# FM-Superregenerative-Receiver-2.net
KiCad netlist of a schematic drawn in EAGLE
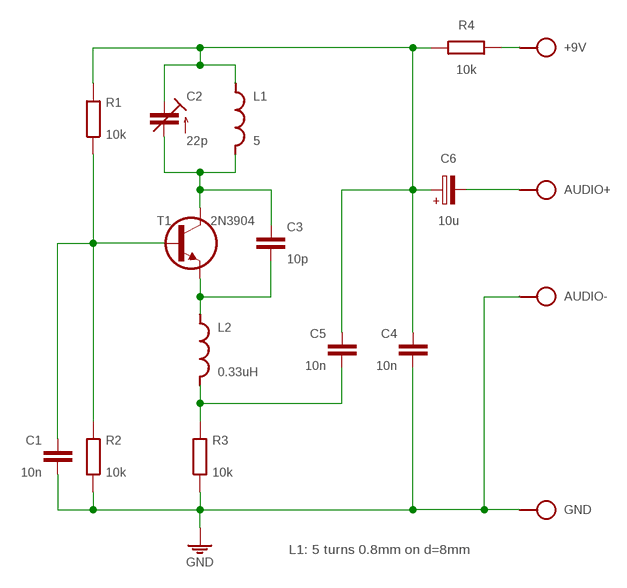
[diagram p0: schematic, sheet 1]

(export (version "E")
  (design (tool "Eeschema 10.0.6"))
  (components
    (comp (ref "+9V")
      (value "SPAD")
      (footprint "eagle-import:SPAD")
      (libsource (lib "eagle-import") (part "SPAD"))
    )
    (comp (ref "AUDIO+")
      (value "SPAD")
      (footprint "eagle-import:SPAD")
      (libsource (lib "eagle-import") (part "SPAD"))
    )
    (comp (ref "AUDIO-")
      (value "SPAD")
      (footprint "eagle-import:SPAD")
      (libsource (lib "eagle-import") (part "SPAD"))
    )
    (comp (ref "C1")
      (value "10n")
      (footprint "eagle-import:C050-025X075")
      (libsource (lib "eagle-import") (part "C050-025X075"))
    )
    (comp (ref "C2")
      (value "22p")
      (footprint "eagle-import:TRIM-2222-808")
      (libsource (lib "eagle-import") (part "C-TR-PH20127"))
    )
    (comp (ref "C3")
      (value "10p")
      (footprint "eagle-import:C050-020X036")
      (libsource (lib "eagle-import") (part "C050-020X036"))
    )
    (comp (ref "C4")
      (value "10n")
      (footprint "eagle-import:C050-025X075")
      (libsource (lib "eagle-import") (part "C050-025X075"))
    )
    (comp (ref "C5")
      (value "10n")
      (footprint "eagle-import:C050-025X075")
      (libsource (lib "eagle-import") (part "C050-025X075"))
    )
    (comp (ref "C6")
      (value "10u")
      (footprint "eagle-import:E2,5-3")
      (libsource (lib "eagle-import") (part "CPOLE2,5-3"))
    )
    (comp (ref "GND")
      (value "SPAD")
      (footprint "eagle-import:SPAD")
      (libsource (lib "eagle-import") (part "SPAD"))
    )
    (comp (ref "L1")
      (value "5")
      (footprint "eagle-import:L-02_5V")
      (libsource (lib "eagle-import") (part "L-SHORT02/5"))
    )
    (comp (ref "L2")
      (value "0.33uH")
      (footprint "eagle-import:L-02_5V")
      (libsource (lib "eagle-import") (part "L-SHORT02/5"))
    )
    (comp (ref "R1")
      (value "10k")
      (footprint "eagle-import:0204_10")
      (libsource (lib "eagle-import") (part "R0204/10"))
    )
    (comp (ref "R2")
      (value "10k")
      (footprint "eagle-import:0204_10")
      (libsource (lib "eagle-import") (part "R0204/10"))
    )
    (comp (ref "R3")
      (value "10k")
      (footprint "eagle-import:0204_10")
      (libsource (lib "eagle-import") (part "R0204/10"))
    )
    (comp (ref "R4")
      (value "10k")
      (footprint "eagle-import:0204_10")
      (libsource (lib "eagle-import") (part "R0204/10"))
    )
    (comp (ref "T1")
      (value "2N3904")
      (footprint "eagle-import:TO92")
      (libsource (lib "eagle-import") (part "2N3904"))
    )
  )
  (nets
    (net (code "1") (name "GND") (class "Default")
      (node (ref "AUDIO-") (pin "1") (pinfunction "P$1_1") (pintype "bidirectional"))
      (node (ref "C1") (pin "2") (pinfunction "2_2") (pintype "passive"))
      (node (ref "C4") (pin "2") (pinfunction "2_2") (pintype "passive"))
      (node (ref "GND") (pin "1") (pinfunction "P$1_1") (pintype "bidirectional"))
      (node (ref "R2") (pin "1") (pinfunction "1_1") (pintype "passive"))
      (node (ref "R3") (pin "1") (pinfunction "1_1") (pintype "passive"))
    )
    (net (code "2") (name "Net-(+9V-P$1)") (class "Default")
      (node (ref "+9V") (pin "1") (pinfunction "P$1_1") (pintype "bidirectional"))
      (node (ref "R4") (pin "1") (pinfunction "1_1") (pintype "passive"))
    )
    (net (code "3") (name "Net-(AUDIO+-P$1)") (class "Default")
      (node (ref "AUDIO+") (pin "1") (pinfunction "P$1_1") (pintype "bidirectional"))
      (node (ref "C6") (pin "-") (pinfunction "-_-") (pintype "passive"))
    )
    (net (code "4") (name "Net-(C2-A)") (class "Default")
      (node (ref "C2") (pin "2") (pinfunction "A_2") (pintype "passive"))
      (node (ref "C3") (pin "1") (pinfunction "1_1") (pintype "passive"))
      (node (ref "L1") (pin "2") (pinfunction "2_2") (pintype "passive"))
      (node (ref "T1") (pin "3") (pinfunction "C_3") (pintype "passive"))
    )
    (net (code "5") (name "Net-(C2-E-Pad1)") (class "Default")
      (node (ref "C2") (pin "1") (pinfunction "E_1") (pintype "passive"))
      (node (ref "C2") (pin "3") (pinfunction "E_3") (pintype "passive"))
      (node (ref "C4") (pin "1") (pinfunction "1_1") (pintype "passive"))
      (node (ref "C5") (pin "1") (pinfunction "1_1") (pintype "passive"))
      (node (ref "C6") (pin "+") (pinfunction "+_+") (pintype "passive"))
      (node (ref "L1") (pin "1") (pinfunction "1_1") (pintype "passive"))
      (node (ref "R1") (pin "2") (pinfunction "2_2") (pintype "passive"))
      (node (ref "R4") (pin "2") (pinfunction "2_2") (pintype "passive"))
    )
    (net (code "6") (name "Net-(C5-Pad2)") (class "Default")
      (node (ref "C5") (pin "2") (pinfunction "2_2") (pintype "passive"))
      (node (ref "L2") (pin "2") (pinfunction "2_2") (pintype "passive"))
      (node (ref "R3") (pin "2") (pinfunction "2_2") (pintype "passive"))
    )
    (net (code "7") (name "Net-(T1-B)") (class "Default")
      (node (ref "C1") (pin "1") (pinfunction "1_1") (pintype "passive"))
      (node (ref "R1") (pin "1") (pinfunction "1_1") (pintype "passive"))
      (node (ref "R2") (pin "2") (pinfunction "2_2") (pintype "passive"))
      (node (ref "T1") (pin "2") (pinfunction "B_2") (pintype "passive"))
    )
    (net (code "8") (name "Net-(T1-E)") (class "Default")
      (node (ref "C3") (pin "2") (pinfunction "2_2") (pintype "passive"))
      (node (ref "L2") (pin "1") (pinfunction "1_1") (pintype "passive"))
      (node (ref "T1") (pin "1") (pinfunction "E_1") (pintype "passive"))
    )
  )
)
